# 12adc_Disp_AIR.net
KiCad netlist of a schematic drawn in EAGLE
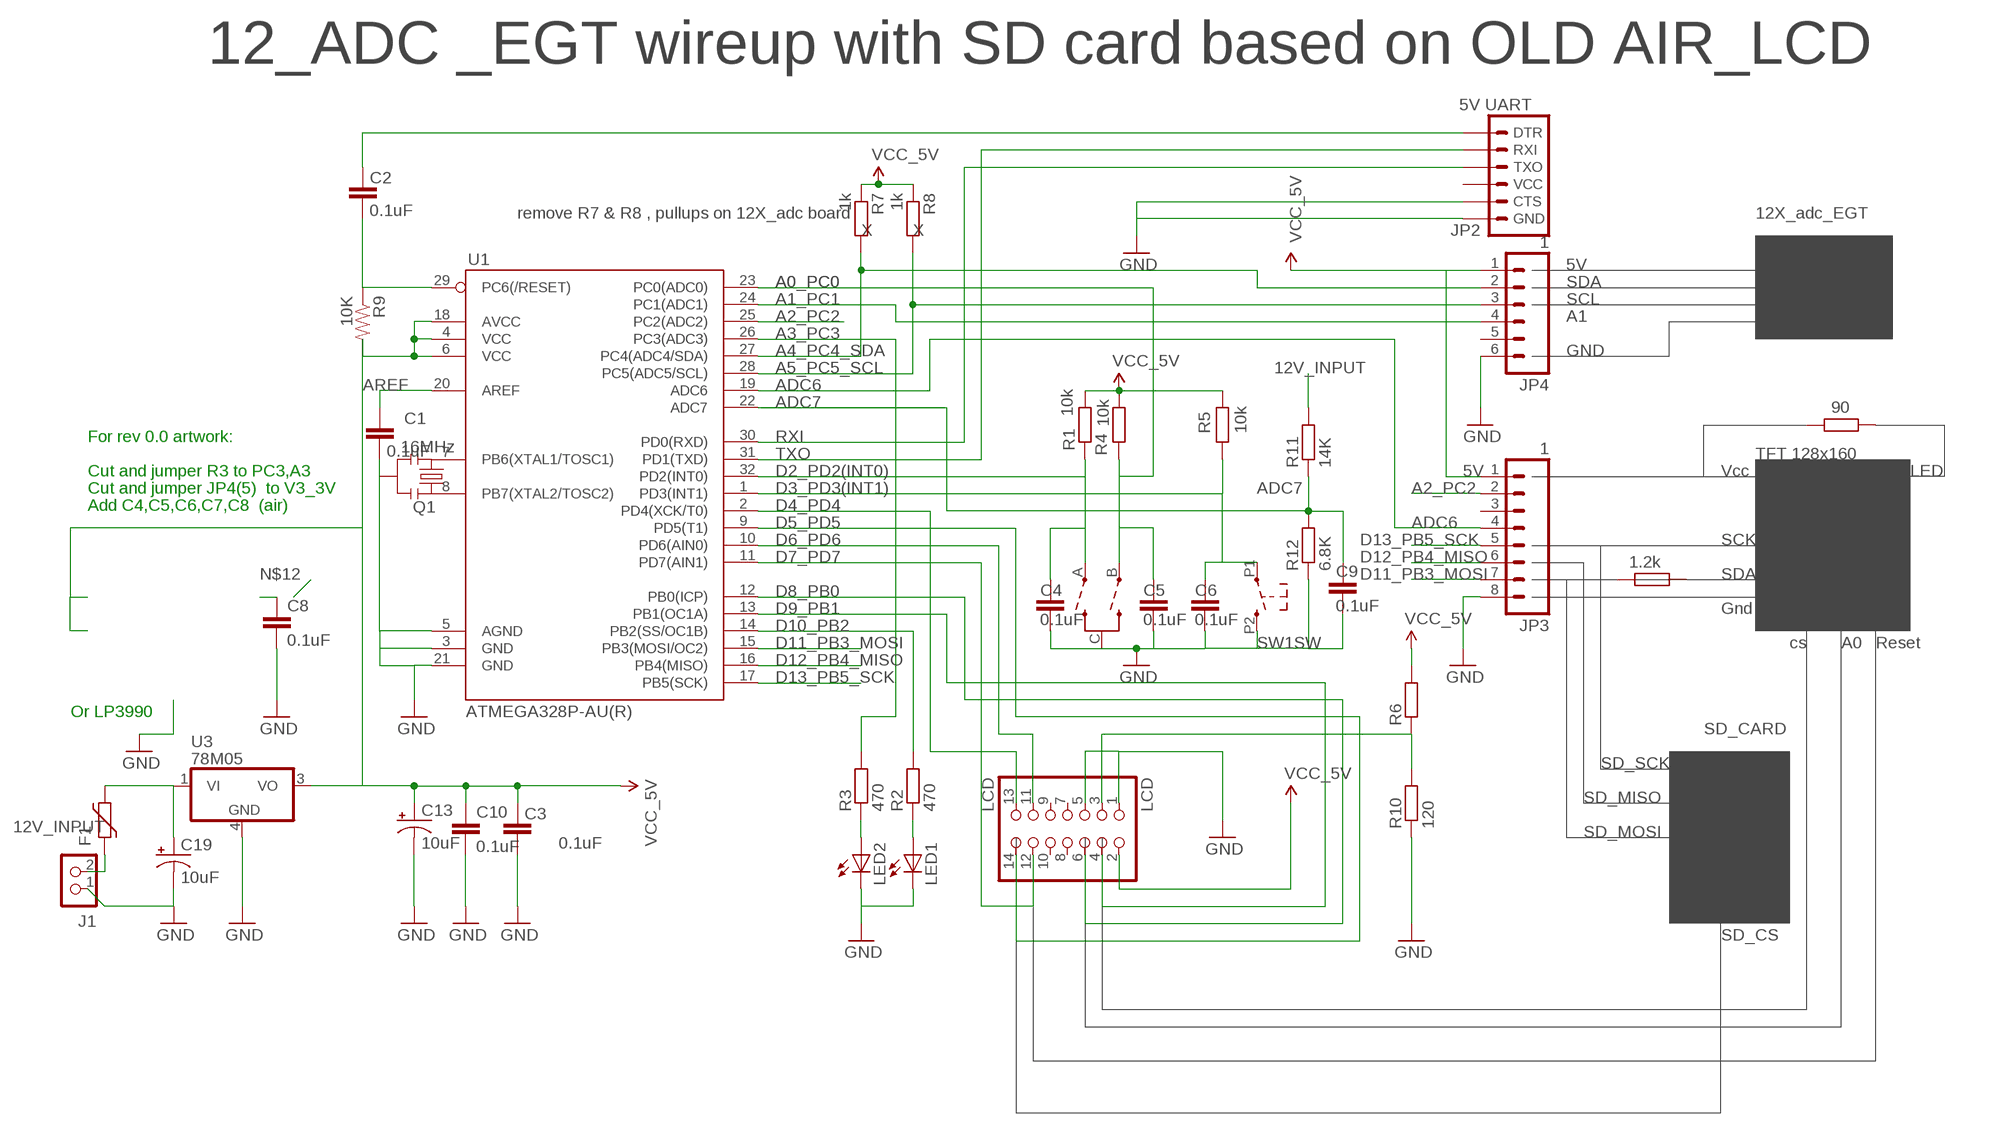
[diagram p0: schematic, sheet 1]

(export (version "E")
  (design (tool "Eeschema 10.0.6"))
  (components
    (comp (ref "C1")
      (value "0.1uF")
      (footprint "eagle-import:0805")
      (libsource (lib "eagle-import") (part "CAP0805"))
    )
    (comp (ref "C2")
      (value "0.1uF")
      (footprint "eagle-import:0805")
      (libsource (lib "eagle-import") (part "CAP0805"))
    )
    (comp (ref "C3")
      (value "0.1uF")
      (footprint "eagle-import:0805")
      (libsource (lib "eagle-import") (part "CAP0805"))
    )
    (comp (ref "C4")
      (value "0.1uF")
      (footprint "eagle-import:0805")
      (libsource (lib "eagle-import") (part "CAP0805"))
    )
    (comp (ref "C5")
      (value "0.1uF")
      (footprint "eagle-import:0805")
      (libsource (lib "eagle-import") (part "CAP0805"))
    )
    (comp (ref "C6")
      (value "0.1uF")
      (footprint "eagle-import:0805")
      (libsource (lib "eagle-import") (part "CAP0805"))
    )
    (comp (ref "C8")
      (value "0.1uF")
      (footprint "eagle-import:0805")
      (libsource (lib "eagle-import") (part "CAP0805"))
    )
    (comp (ref "C9")
      (value "0.1uF")
      (footprint "eagle-import:0805")
      (libsource (lib "eagle-import") (part "CAP0805"))
    )
    (comp (ref "C10")
      (value "0.1uF")
      (footprint "eagle-import:0805")
      (libsource (lib "eagle-import") (part "CAP0805"))
    )
    (comp (ref "C13")
      (value "10uF")
      (footprint "eagle-import:EIA3216")
      (libsource (lib "eagle-import") (part "CAP_POL1206"))
    )
    (comp (ref "C19")
      (value "10uF")
      (footprint "eagle-import:EIA7343")
      (libsource (lib "eagle-import") (part "CAP_POL7343"))
    )
    (comp (ref "F1")
      (value "FUSE_PTC-0805")
      (footprint "eagle-import:PTC0805")
      (libsource (lib "eagle-import") (part "FUSE_PTC-0805"))
    )
    (comp (ref "J1")
      (value "12V input")
      (footprint "eagle-import:M1X2")
      (libsource (lib "eagle-import") (part "CON_HEADER_1X02-PTH"))
    )
    (comp (ref "JP2")
      (value "5V UART")
      (footprint "eagle-import:1X06")
      (libsource (lib "eagle-import") (part "ARDUINO_SERIAL_PROGRAMPTH"))
    )
    (comp (ref "JP3")
      (value "1")
      (footprint "eagle-import:1X08")
      (libsource (lib "eagle-import") (part "M081X08"))
    )
    (comp (ref "JP4")
      (value "1")
      (footprint "eagle-import:1X06")
      (libsource (lib "eagle-import") (part "M06SIP"))
    )
    (comp (ref "LCD")
      (value "LCD")
      (footprint "eagle-import:2X07")
      (libsource (lib "eagle-import") (part "PINHD-2X7"))
    )
    (comp (ref "LED1")
      (value "LED-5MM")
      (footprint "eagle-import:LED-5MM")
      (libsource (lib "eagle-import") (part "LED-5MM"))
    )
    (comp (ref "LED2")
      (value "LED-5MM")
      (footprint "eagle-import:LED-5MM")
      (libsource (lib "eagle-import") (part "LED-5MM"))
    )
    (comp (ref "Q1")
      (value "16MHz")
      (footprint "eagle-import:RESONATOR-SMD")
      (libsource (lib "eagle-import") (part "RESONATORSMD"))
    )
    (comp (ref "R1")
      (value "10k")
      (footprint "eagle-import:R603")
      (libsource (lib "eagle-import") (part "RESISTOR-0603"))
    )
    (comp (ref "R2")
      (value "470")
      (footprint "eagle-import:R603")
      (libsource (lib "eagle-import") (part "RESISTOR-0603"))
    )
    (comp (ref "R3")
      (value "470")
      (footprint "eagle-import:R603")
      (libsource (lib "eagle-import") (part "RESISTOR-0603"))
    )
    (comp (ref "R4")
      (value "10k")
      (footprint "eagle-import:R603")
      (libsource (lib "eagle-import") (part "RESISTOR-0603"))
    )
    (comp (ref "R5")
      (value "10k")
      (footprint "eagle-import:R603")
      (libsource (lib "eagle-import") (part "RESISTOR-0603"))
    )
    (comp (ref "R6")
      (value "RESISTOR-0603")
      (footprint "eagle-import:R603")
      (libsource (lib "eagle-import") (part "RESISTOR-0603"))
    )
    (comp (ref "R7")
      (value "1k")
      (footprint "eagle-import:R603")
      (libsource (lib "eagle-import") (part "RESISTOR-0603"))
    )
    (comp (ref "R8")
      (value "1k")
      (footprint "eagle-import:R603")
      (libsource (lib "eagle-import") (part "RESISTOR-0603"))
    )
    (comp (ref "R9")
      (value "10K")
      (footprint "eagle-import:0603")
      (libsource (lib "eagle-import") (part "RESISTOR0603"))
    )
    (comp (ref "R10")
      (value "120")
      (footprint "eagle-import:R603")
      (libsource (lib "eagle-import") (part "RESISTOR-0603"))
    )
    (comp (ref "R11")
      (value "14K")
      (footprint "eagle-import:R603")
      (libsource (lib "eagle-import") (part "RESISTOR-0603"))
    )
    (comp (ref "R12")
      (value "6.8K")
      (footprint "eagle-import:R603")
      (libsource (lib "eagle-import") (part "RESISTOR-0603"))
    )
    (comp (ref "R13")
      (value "1.2k")
      (footprint "eagle-import:R603")
      (libsource (lib "eagle-import") (part "RESISTOR-0603"))
    )
    (comp (ref "R14")
      (value "90")
      (footprint "eagle-import:R603")
      (libsource (lib "eagle-import") (part "RESISTOR-0603"))
    )
    (comp (ref "SW1")
      (value "ENCODER_SW1-PEC12")
      (footprint "eagle-import:PEC12_INCREMENTAL_ENCODER")
      (libsource (lib "eagle-import") (part "ENCODER_SW1-PEC12"))
    )
    (comp (ref "U1")
      (value "ATMEGA328P-AU(R)")
      (footprint "eagle-import:TQFP32-08")
      (libsource (lib "eagle-import") (part "ATMEGA168"))
    )
    (comp (ref "U3")
      (value "78M05")
      (footprint "eagle-import:DPACK")
      (libsource (lib "eagle-import") (part "78MXXL"))
    )
  )
  (nets
    (net (code "1") (name "/12V_INPUT") (class "Default")
      (node (ref "C19") (pin "A") (pinfunction "+_A") (pintype "passive"))
      (node (ref "F1") (pin "2") (pinfunction "2_2") (pintype "passive"))
      (node (ref "R11") (pin "2") (pinfunction "2_2") (pintype "passive"))
      (node (ref "U3") (pin "1") (pinfunction "VI_1") (pintype "input"))
    )
    (net (code "2") (name "/A0_PC0") (class "Default")
      (node (ref "C5") (pin "2") (pinfunction "2_2") (pintype "passive"))
      (node (ref "R4") (pin "2") (pinfunction "2_2") (pintype "passive"))
      (node (ref "SW1") (pin "B") (pinfunction "B_B") (pintype "passive"))
      (node (ref "U1") (pin "23") (pinfunction "PC0(ADC0)_23") (pintype "bidirectional"))
    )
    (net (code "3") (name "/A1_PC1") (class "Default")
      (node (ref "JP4") (pin "4") (pinfunction "4_4") (pintype "passive"))
      (node (ref "U1") (pin "24") (pinfunction "PC1(ADC1)_24") (pintype "bidirectional"))
    )
    (net (code "4") (name "/A2_PC2") (class "Default")
      (node (ref "JP3") (pin "2") (pinfunction "2_2") (pintype "passive"))
      (node (ref "U1") (pin "25") (pinfunction "PC2(ADC2)_25") (pintype "bidirectional"))
    )
    (net (code "5") (name "/A3_PC3") (class "Default")
      (node (ref "R3") (pin "2") (pinfunction "2_2") (pintype "passive"))
      (node (ref "U1") (pin "26") (pinfunction "PC3(ADC3)_26") (pintype "bidirectional"))
    )
    (net (code "6") (name "/A4_PC4_SDA") (class "Default")
      (node (ref "JP4") (pin "2") (pinfunction "2_2") (pintype "passive"))
      (node (ref "R7") (pin "2") (pinfunction "2_2") (pintype "passive"))
      (node (ref "U1") (pin "27") (pinfunction "PC4(ADC4/SDA)_27") (pintype "bidirectional"))
    )
    (net (code "7") (name "/A5_PC5_SCL") (class "Default")
      (node (ref "JP4") (pin "3") (pinfunction "3_3") (pintype "passive"))
      (node (ref "R8") (pin "2") (pinfunction "2_2") (pintype "passive"))
      (node (ref "U1") (pin "28") (pinfunction "PC5(ADC5/SCL)_28") (pintype "bidirectional"))
    )
    (net (code "8") (name "/ADC6") (class "Default")
      (node (ref "JP3") (pin "4") (pinfunction "4_4") (pintype "passive"))
      (node (ref "U1") (pin "19") (pinfunction "ADC6_19") (pintype "bidirectional"))
    )
    (net (code "9") (name "/ADC7") (class "Default")
      (node (ref "C9") (pin "1") (pinfunction "1_1") (pintype "passive"))
      (node (ref "R11") (pin "1") (pinfunction "1_1") (pintype "passive"))
      (node (ref "R12") (pin "2") (pinfunction "2_2") (pintype "passive"))
      (node (ref "U1") (pin "22") (pinfunction "ADC7_22") (pintype "bidirectional"))
    )
    (net (code "10") (name "/AREF") (class "Default")
      (node (ref "C1") (pin "2") (pinfunction "2_2") (pintype "passive"))
      (node (ref "U1") (pin "20") (pinfunction "AREF_20") (pintype "bidirectional"))
    )
    (net (code "11") (name "/D2_PD2(INT0)") (class "Default")
      (node (ref "C4") (pin "2") (pinfunction "2_2") (pintype "passive"))
      (node (ref "R1") (pin "1") (pinfunction "1_1") (pintype "passive"))
      (node (ref "SW1") (pin "A") (pinfunction "A_A") (pintype "passive"))
      (node (ref "U1") (pin "32") (pinfunction "PD2(INT0)_32") (pintype "bidirectional"))
    )
    (net (code "12") (name "/D3_PD3(INT1)") (class "Default")
      (node (ref "C6") (pin "2") (pinfunction "2_2") (pintype "passive"))
      (node (ref "R5") (pin "1") (pinfunction "1_1") (pintype "passive"))
      (node (ref "SW1") (pin "P1") (pinfunction "1_P1") (pintype "passive"))
      (node (ref "U1") (pin "1") (pinfunction "PD3(INT1)_1") (pintype "bidirectional"))
    )
    (net (code "13") (name "/D4_PD4") (class "Default")
      (node (ref "LCD") (pin "13") (pinfunction "13_13") (pintype "passive"))
      (node (ref "U1") (pin "2") (pinfunction "PD4(XCK/T0)_2") (pintype "bidirectional"))
    )
    (net (code "14") (name "/D5_PD5") (class "Default")
      (node (ref "LCD") (pin "14") (pinfunction "14_14") (pintype "passive"))
      (node (ref "U1") (pin "9") (pinfunction "PD5(T1)_9") (pintype "bidirectional"))
    )
    (net (code "15") (name "/D6_PD6") (class "Default")
      (node (ref "LCD") (pin "11") (pinfunction "11_11") (pintype "passive"))
      (node (ref "U1") (pin "10") (pinfunction "PD6(AIN0)_10") (pintype "bidirectional"))
    )
    (net (code "16") (name "/D7_PD7") (class "Default")
      (node (ref "LCD") (pin "12") (pinfunction "12_12") (pintype "passive"))
      (node (ref "U1") (pin "11") (pinfunction "PD7(AIN1)_11") (pintype "bidirectional"))
    )
    (net (code "17") (name "/D8_PB0") (class "Default")
      (node (ref "LCD") (pin "6") (pinfunction "6_6") (pintype "passive"))
      (node (ref "U1") (pin "12") (pinfunction "PB0(ICP)_12") (pintype "bidirectional"))
    )
    (net (code "18") (name "/D9_PB1") (class "Default")
      (node (ref "LCD") (pin "4") (pinfunction "4_4") (pintype "passive"))
      (node (ref "U1") (pin "13") (pinfunction "PB1(OC1A)_13") (pintype "bidirectional"))
    )
    (net (code "19") (name "/D10_PB2") (class "Default")
      (node (ref "R2") (pin "2") (pinfunction "2_2") (pintype "passive"))
      (node (ref "U1") (pin "14") (pinfunction "PB2(SS/OC1B)_14") (pintype "bidirectional"))
    )
    (net (code "20") (name "/D11_PB3_MOSI") (class "Default")
      (node (ref "JP3") (pin "7") (pinfunction "7_7") (pintype "passive"))
      (node (ref "U1") (pin "15") (pinfunction "PB3(MOSI/OC2)_15") (pintype "bidirectional"))
    )
    (net (code "21") (name "/D12_PB4_MISO") (class "Default")
      (node (ref "JP3") (pin "6") (pinfunction "6_6") (pintype "passive"))
      (node (ref "U1") (pin "16") (pinfunction "PB4(MISO)_16") (pintype "bidirectional"))
    )
    (net (code "22") (name "/D13_PB5_SCK") (class "Default")
      (node (ref "JP3") (pin "5") (pinfunction "5_5") (pintype "passive"))
      (node (ref "U1") (pin "17") (pinfunction "PB5(SCK)_17") (pintype "bidirectional"))
    )
    (net (code "23") (name "/N$12") (class "Default")
      (node (ref "C8") (pin "1") (pinfunction "1_1") (pintype "passive"))
    )
    (net (code "24") (name "/RXI") (class "Default")
      (node (ref "JP2") (pin "3") (pinfunction "TXO_3") (pintype "passive"))
      (node (ref "U1") (pin "30") (pinfunction "PD0(RXD)_30") (pintype "bidirectional"))
    )
    (net (code "25") (name "/TXO") (class "Default")
      (node (ref "JP2") (pin "2") (pinfunction "RXI_2") (pintype "passive"))
      (node (ref "U1") (pin "31") (pinfunction "PD1(TXD)_31") (pintype "bidirectional"))
    )
    (net (code "26") (name "GND") (class "Default")
      (node (ref "C1") (pin "1") (pinfunction "1_1") (pintype "passive"))
      (node (ref "C10") (pin "2") (pinfunction "2_2") (pintype "passive"))
      (node (ref "C13") (pin "C") (pinfunction "-_C") (pintype "passive"))
      (node (ref "C19") (pin "C") (pinfunction "-_C") (pintype "passive"))
      (node (ref "C3") (pin "1") (pinfunction "1_1") (pintype "passive"))
      (node (ref "C4") (pin "1") (pinfunction "1_1") (pintype "passive"))
      (node (ref "C5") (pin "1") (pinfunction "1_1") (pintype "passive"))
      (node (ref "C6") (pin "1") (pinfunction "1_1") (pintype "passive"))
      (node (ref "C8") (pin "2") (pinfunction "2_2") (pintype "passive"))
      (node (ref "C9") (pin "2") (pinfunction "2_2") (pintype "passive"))
      (node (ref "J1") (pin "1") (pinfunction "1_1") (pintype "passive"))
      (node (ref "JP2") (pin "5") (pinfunction "CTS_5") (pintype "passive"))
      (node (ref "JP2") (pin "6") (pinfunction "GND_6") (pintype "passive"))
      (node (ref "JP3") (pin "8") (pinfunction "8_8") (pintype "passive"))
      (node (ref "JP4") (pin "6") (pinfunction "6_6") (pintype "passive"))
      (node (ref "LCD") (pin "1") (pinfunction "1_1") (pintype "passive"))
      (node (ref "LCD") (pin "5") (pinfunction "5_5") (pintype "passive"))
      (node (ref "LED1") (pin "K") (pinfunction "C_K") (pintype "passive"))
      (node (ref "LED2") (pin "K") (pinfunction "C_K") (pintype "passive"))
      (node (ref "Q1") (pin "2") (pinfunction "2_2") (pintype "passive"))
      (node (ref "R10") (pin "1") (pinfunction "1_1") (pintype "passive"))
      (node (ref "R12") (pin "1") (pinfunction "1_1") (pintype "passive"))
      (node (ref "SW1") (pin "C") (pinfunction "C_C") (pintype "passive"))
      (node (ref "SW1") (pin "P2") (pinfunction "2_P2") (pintype "passive"))
      (node (ref "U1") (pin "21") (pinfunction "GND_21") (pintype "bidirectional"))
      (node (ref "U1") (pin "3") (pinfunction "GND_3") (pintype "bidirectional"))
      (node (ref "U1") (pin "5") (pinfunction "AGND_5") (pintype "bidirectional"))
      (node (ref "U3") (pin "4") (pinfunction "GND_4") (pintype "passive"))
    )
    (net (code "27") (name "Net-(F1-Pad1)") (class "Default")
      (node (ref "F1") (pin "1") (pinfunction "1_1") (pintype "passive"))
      (node (ref "J1") (pin "2") (pinfunction "2_2") (pintype "passive"))
    )
    (net (code "28") (name "Net-(JP2-DTR)") (class "Default")
      (node (ref "C2") (pin "2") (pinfunction "2_2") (pintype "passive"))
      (node (ref "JP2") (pin "1") (pinfunction "DTR_1") (pintype "passive"))
    )
    (net (code "29") (name "Net-(LCD-Pad3)") (class "Default")
      (node (ref "LCD") (pin "3") (pinfunction "3_3") (pintype "passive"))
      (node (ref "R10") (pin "2") (pinfunction "2_2") (pintype "passive"))
      (node (ref "R6") (pin "1") (pinfunction "1_1") (pintype "passive"))
    )
    (net (code "30") (name "Net-(LED1-PadA)") (class "Default")
      (node (ref "LED1") (pin "A") (pinfunction "A_A") (pintype "passive"))
      (node (ref "R2") (pin "1") (pinfunction "1_1") (pintype "passive"))
    )
    (net (code "31") (name "Net-(LED2-PadA)") (class "Default")
      (node (ref "LED2") (pin "A") (pinfunction "A_A") (pintype "passive"))
      (node (ref "R3") (pin "1") (pinfunction "1_1") (pintype "passive"))
    )
    (net (code "32") (name "Net-(U1-PB6(XTAL1{slash}TOSC1))") (class "Default")
      (node (ref "Q1") (pin "3") (pinfunction "3_3") (pintype "passive"))
      (node (ref "U1") (pin "7") (pinfunction "PB6(XTAL1/TOSC1)_7") (pintype "bidirectional"))
    )
    (net (code "33") (name "Net-(U1-PB7(XTAL2{slash}TOSC2))") (class "Default")
      (node (ref "Q1") (pin "1") (pinfunction "1_1") (pintype "passive"))
      (node (ref "U1") (pin "8") (pinfunction "PB7(XTAL2/TOSC2)_8") (pintype "bidirectional"))
    )
    (net (code "34") (name "Net-(U1-PC6({slash}RESET))") (class "Default")
      (node (ref "C2") (pin "1") (pinfunction "1_1") (pintype "passive"))
      (node (ref "R9") (pin "1") (pinfunction "1_1") (pintype "passive"))
      (node (ref "U1") (pin "29") (pinfunction "PC6(/RESET)_29") (pintype "bidirectional"))
    )
    (net (code "35") (name "VCC_5V") (class "Default")
      (node (ref "C10") (pin "1") (pinfunction "1_1") (pintype "passive"))
      (node (ref "C13") (pin "A") (pinfunction "+_A") (pintype "passive"))
      (node (ref "C3") (pin "2") (pinfunction "2_2") (pintype "passive"))
      (node (ref "JP3") (pin "1") (pinfunction "1_1") (pintype "passive"))
      (node (ref "JP4") (pin "1") (pinfunction "1_1") (pintype "passive"))
      (node (ref "LCD") (pin "2") (pinfunction "2_2") (pintype "passive"))
      (node (ref "R1") (pin "2") (pinfunction "2_2") (pintype "passive"))
      (node (ref "R4") (pin "1") (pinfunction "1_1") (pintype "passive"))
      (node (ref "R5") (pin "2") (pinfunction "2_2") (pintype "passive"))
      (node (ref "R6") (pin "2") (pinfunction "2_2") (pintype "passive"))
      (node (ref "R7") (pin "1") (pinfunction "1_1") (pintype "passive"))
      (node (ref "R8") (pin "1") (pinfunction "1_1") (pintype "passive"))
      (node (ref "R9") (pin "2") (pinfunction "2_2") (pintype "passive"))
      (node (ref "U1") (pin "18") (pinfunction "AVCC_18") (pintype "bidirectional"))
      (node (ref "U1") (pin "4") (pinfunction "VCC_4") (pintype "bidirectional"))
      (node (ref "U1") (pin "6") (pinfunction "VCC_6") (pintype "bidirectional"))
      (node (ref "U3") (pin "3") (pinfunction "VO_3") (pintype "passive"))
    )
    (net (code "36") (name "unconnected-(JP2-VCC-Pad4)") (class "Default")
      (node (ref "JP2") (pin "4") (pinfunction "VCC_4") (pintype "passive"))
    )
    (net (code "37") (name "unconnected-(JP3-Pad3)") (class "Default")
      (node (ref "JP3") (pin "3") (pinfunction "3_3") (pintype "passive"))
    )
    (net (code "38") (name "unconnected-(JP4-Pad5)") (class "Default")
      (node (ref "JP4") (pin "5") (pinfunction "5_5") (pintype "passive"))
    )
    (net (code "39") (name "unconnected-(LCD-Pad7)") (class "Default")
      (node (ref "LCD") (pin "7") (pinfunction "7_7") (pintype "passive"))
    )
    (net (code "40") (name "unconnected-(LCD-Pad8)") (class "Default")
      (node (ref "LCD") (pin "8") (pinfunction "8_8") (pintype "passive"))
    )
    (net (code "41") (name "unconnected-(LCD-Pad9)") (class "Default")
      (node (ref "LCD") (pin "9") (pinfunction "9_9") (pintype "passive"))
    )
    (net (code "42") (name "unconnected-(LCD-Pad10)") (class "Default")
      (node (ref "LCD") (pin "10") (pinfunction "10_10") (pintype "passive"))
    )
    (net (code "43") (name "unconnected-(R13-Pad1)") (class "Default")
      (node (ref "R13") (pin "1") (pinfunction "1_1") (pintype "passive"))
    )
    (net (code "44") (name "unconnected-(R13-Pad2)") (class "Default")
      (node (ref "R13") (pin "2") (pinfunction "2_2") (pintype "passive"))
    )
    (net (code "45") (name "unconnected-(R14-Pad1)") (class "Default")
      (node (ref "R14") (pin "1") (pinfunction "1_1") (pintype "passive"))
    )
    (net (code "46") (name "unconnected-(R14-Pad2)") (class "Default")
      (node (ref "R14") (pin "2") (pinfunction "2_2") (pintype "passive"))
    )
  )
)
